# DIYBadgeKit-v10.net
KiCad netlist of a schematic drawn in EAGLE
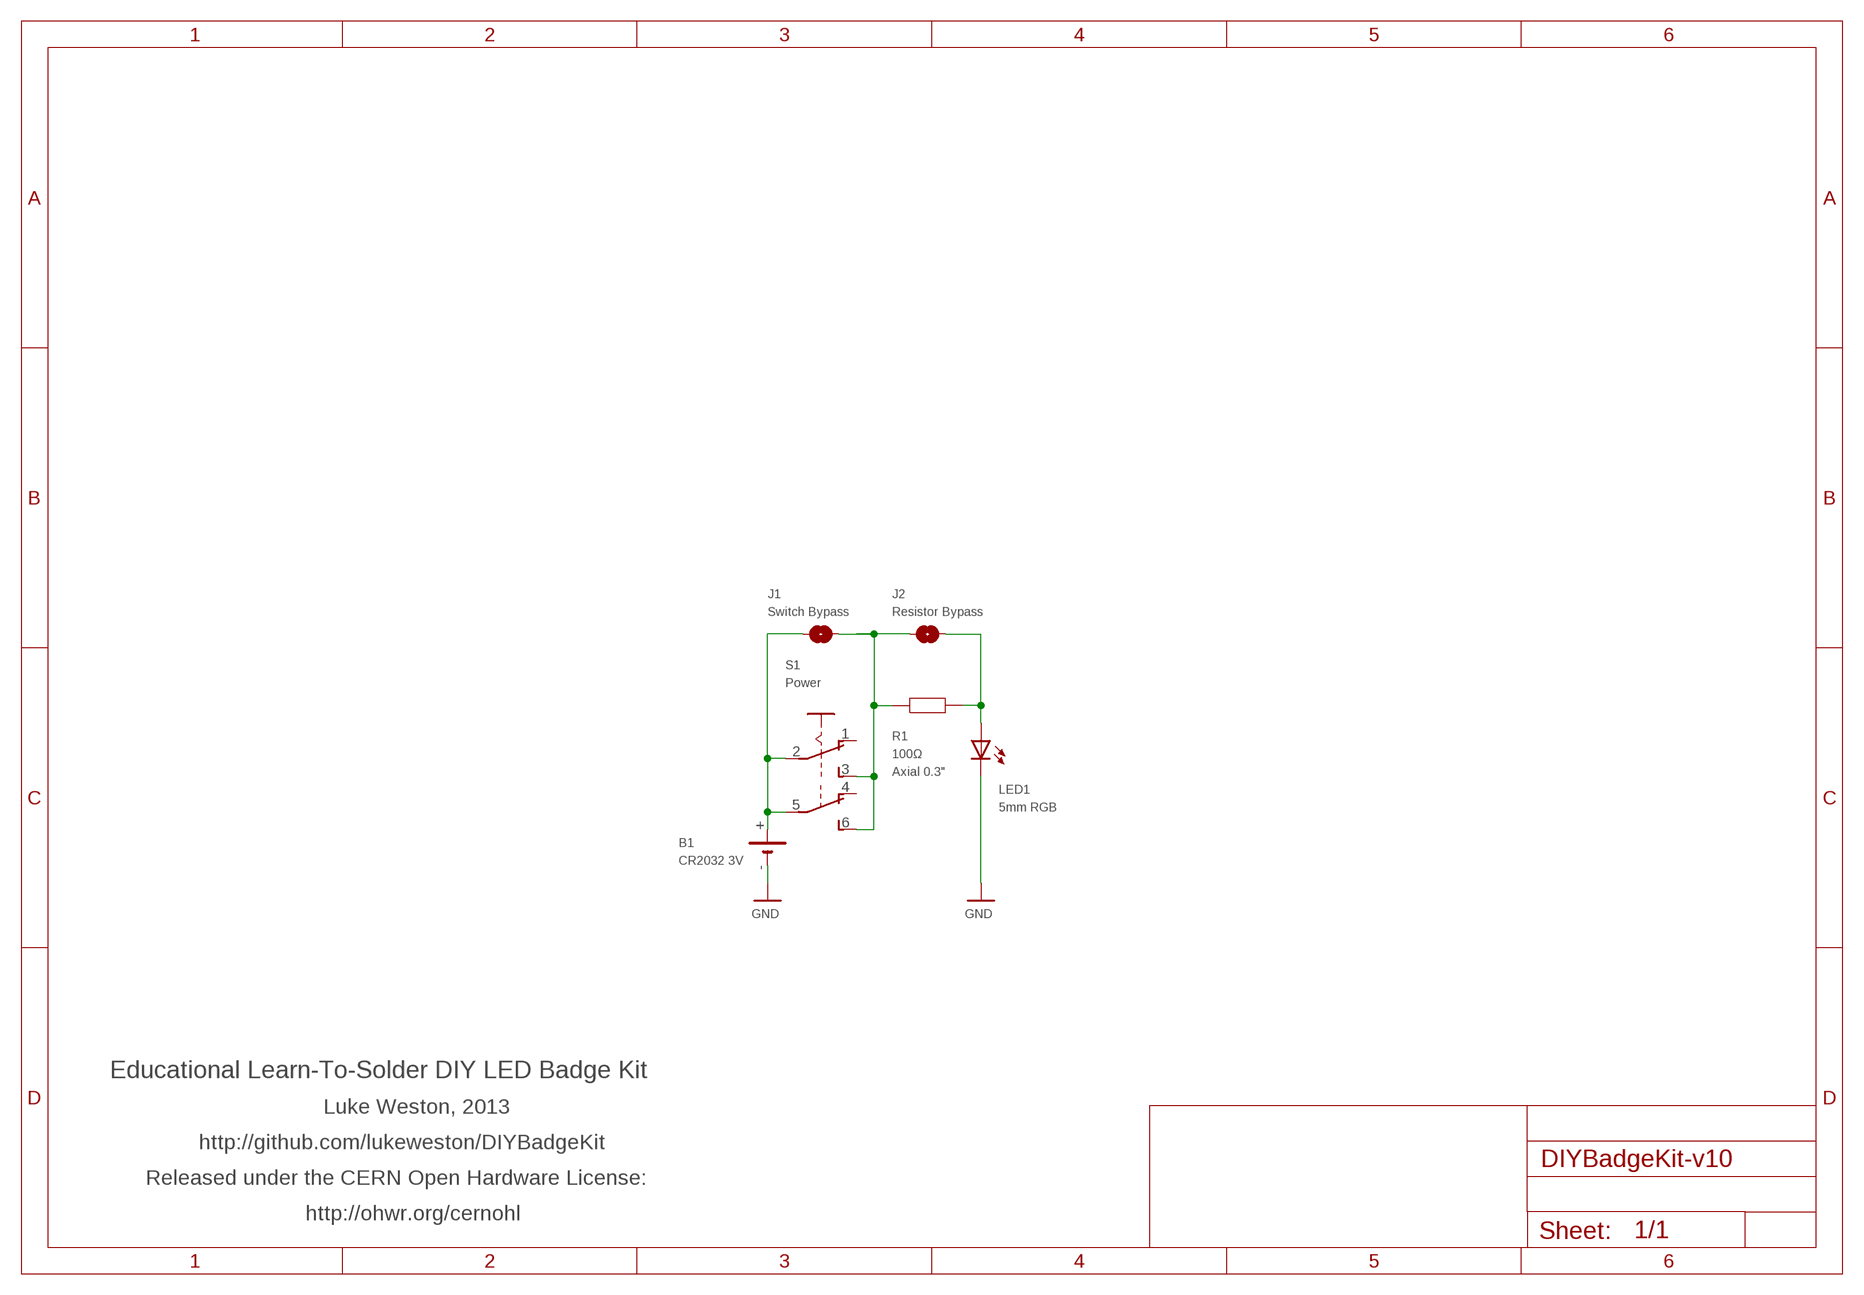
[diagram p0: schematic, sheet 1]

(export (version "E")
  (design (tool "Eeschema 10.0.6"))
  (components
    (comp (ref "B1")
      (value "CR2032 3V")
      (footprint "eagle-import:B2430UNI")
      (libsource (lib "eagle-import") (part "B2430UNI"))
    )
    (comp (ref "J1")
      (value "Switch Bypass")
      (footprint "eagle-import:SJ")
      (libsource (lib "eagle-import") (part "SJ"))
    )
    (comp (ref "J2")
      (value "Resistor Bypass")
      (footprint "eagle-import:SJ")
      (libsource (lib "eagle-import") (part "SJ"))
    )
    (comp (ref "LED1")
      (value "5mm RGB")
      (footprint "eagle-import:LED5MM")
      (libsource (lib "eagle-import") (part "LED5MM"))
    )
    (comp (ref "R1")
      (value "100Ω")
      (footprint "eagle-import:AXIAL-0.3")
      (fields (field (name "PACKAGE") "Axial 0.3\""))
      (libsource (lib "eagle-import") (part "RESISTORPTH1"))
    )
    (comp (ref "S1")
      (value "Power")
      (footprint "eagle-import:A68-A31")
      (libsource (lib "eagle-import") (part "A68-A31"))
    )
  )
  (nets
    (net (code "1") (name "GND") (class "Default")
      (node (ref "B1") (pin "-") (pinfunction "-_-") (pintype "passive"))
      (node (ref "B1") (pin "-@1") (pinfunction "-_-@1") (pintype "passive"))
      (node (ref "LED1") (pin "K") (pinfunction "C_K") (pintype "passive"))
    )
    (net (code "2") (name "Net-(R1-1)") (class "Default")
      (node (ref "J1") (pin "2") (pinfunction "2_2") (pintype "passive"))
      (node (ref "J2") (pin "1") (pinfunction "1_1") (pintype "passive"))
      (node (ref "R1") (pin "P$1") (pinfunction "1_P$1") (pintype "passive"))
      (node (ref "S1") (pin "3") (pinfunction "S_3") (pintype "passive"))
      (node (ref "S1") (pin "6") (pinfunction "S_6") (pintype "passive"))
    )
    (net (code "3") (name "Net-(R1-2)") (class "Default")
      (node (ref "J2") (pin "2") (pinfunction "2_2") (pintype "passive"))
      (node (ref "LED1") (pin "A") (pinfunction "A_A") (pintype "passive"))
      (node (ref "R1") (pin "P$2") (pinfunction "2_P$2") (pintype "passive"))
    )
    (net (code "4") (name "Net-(S1A-P)") (class "Default")
      (node (ref "B1") (pin "+") (pinfunction "+_+") (pintype "passive"))
      (node (ref "B1") (pin "+@1") (pinfunction "+_+@1") (pintype "passive"))
      (node (ref "B1") (pin "+@2") (pinfunction "+_+@2") (pintype "passive"))
      (node (ref "B1") (pin "+@3") (pinfunction "+_+@3") (pintype "passive"))
      (node (ref "B1") (pin "+@4") (pinfunction "+_+@4") (pintype "passive"))
      (node (ref "J1") (pin "1") (pinfunction "1_1") (pintype "passive"))
      (node (ref "S1") (pin "2") (pinfunction "P_2") (pintype "passive"))
      (node (ref "S1") (pin "5") (pinfunction "P_5") (pintype "passive"))
    )
    (net (code "5") (name "unconnected-(S1A-O-Pad1)") (class "Default")
      (node (ref "S1") (pin "1") (pinfunction "O_1") (pintype "passive"))
    )
    (net (code "6") (name "unconnected-(S1B-O-Pad4)") (class "Default")
      (node (ref "S1") (pin "4") (pinfunction "O_4") (pintype "passive"))
    )
  )
)
